# ap-pam-v3_2.net
KiCad netlist of a schematic drawn in Altium Designer
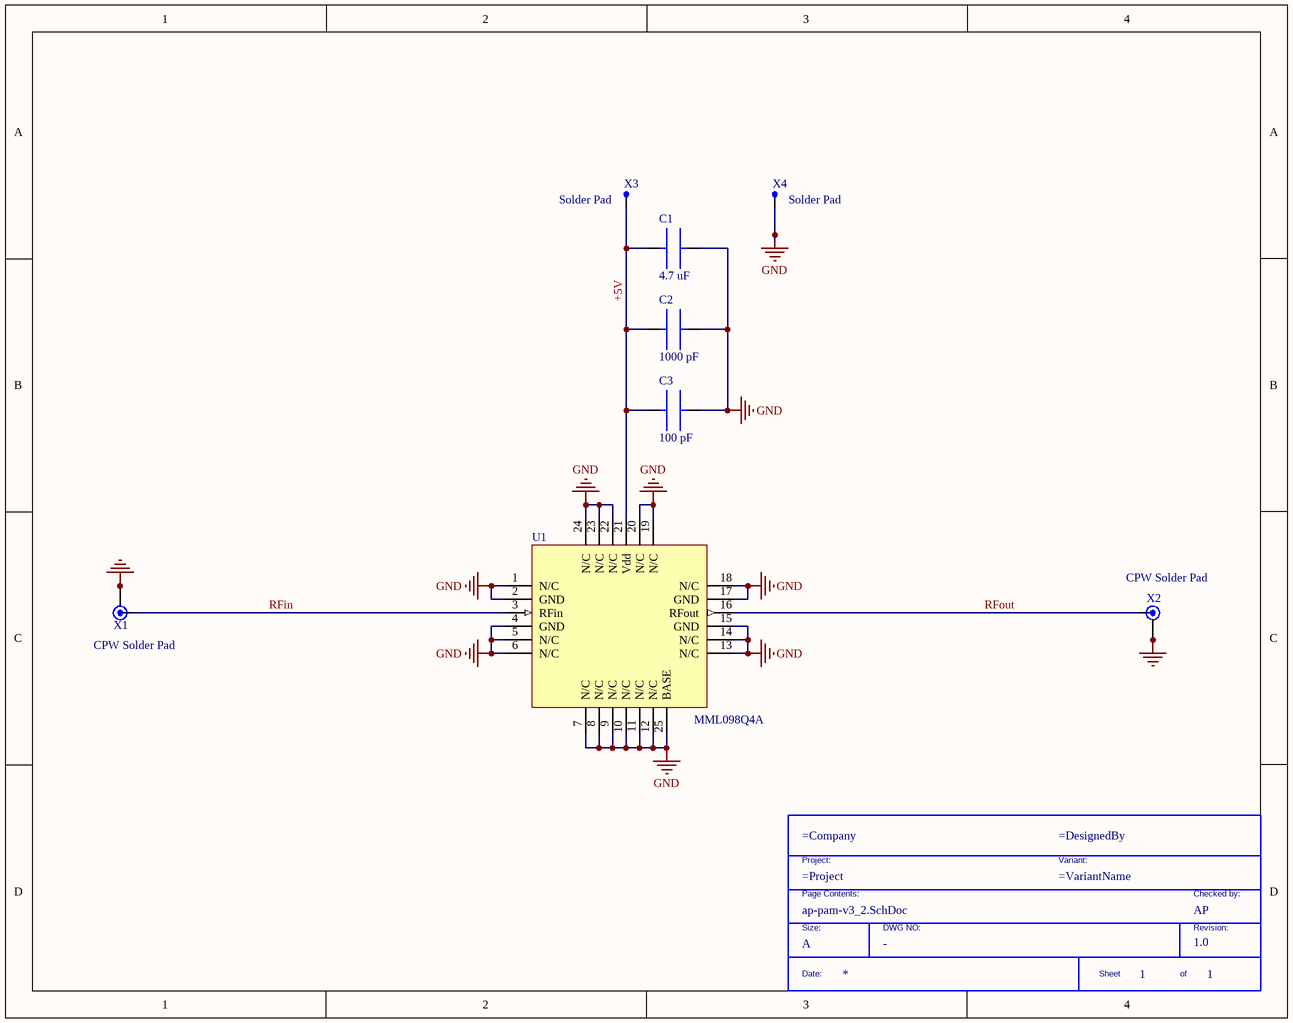
[diagram p0: ap-pam-v3_2.SchDoc]

(export (version "E")
  (design (tool "Eeschema 10.0.6"))
  (components
    (comp (ref "*")
      (value "~")
      (description "Standard Title Block")
      (fields (field (name "DWG NO") "-") (field (name "SIZE") "A") (field (name "CHECKED BY") "AP"))
      (libsource (lib "ap-pam") (part "TitleBlock"))
    )
    (comp (ref "C1")
      (value "4.7 uF")
      (footprint "C4_7uF")
      (fields
        (field (name "MANUFACTURER") "Vishay Sprague")
        (field (name "MANUFACTURER PART NUMBER") "TH3A475K010C2900")
      )
      (libsource (lib "ap-pam") (part "TH3A475K010C2900"))
    )
    (comp (ref "C2")
      (value "1000 pF")
      (footprint "C1000pF")
      (fields
        (field (name "MANUFACTURER") "Murata")
        (field (name "MANUFACTURER PART NUMBER") "GCM1885C1H102FA16D")
      )
      (libsource (lib "ap-pam") (part "GCM1885C1H102FA16D"))
    )
    (comp (ref "C3")
      (value "100 pF")
      (footprint "C100pF")
      (description "Multilayer Ceramic Capacitors MLCC - SMD/SMT 100 pF 100 VDC 1% 0402 C0G (NP0)")
      (fields
        (field (name "MANUFACTURER") "Murata")
        (field (name "MANUFACTURER PART NUMBER") "GRM1555C2A101FA01D")
      )
      (libsource (lib "ap-pam") (part "GRM1555C2A101FA01D"))
    )
    (comp (ref "U1")
      (value "MML098Q4A")
      (footprint "MML098Q4A")
      (libsource (lib "ap-pam") (part "MML098Q4A"))
    )
    (comp (ref "X1")
      (value "CPW Solder Pad")
      (footprint "CPW Edge Connector")
      (description "Solder pad for RF Coplanar Waveguide Rogers 4350B Thickness 0.020\" Copper 1oz")
      (libsource (lib "ap-pam") (part "RF  CPW Solder Pad"))
    )
    (comp (ref "X2")
      (value "CPW Solder Pad")
      (footprint "CPW Edge Connector")
      (description "Solder pad for RF Coplanar Waveguide Rogers 4350B Thickness 0.020\" Copper 1oz")
      (libsource (lib "ap-pam") (part "RF  CPW Solder Pad"))
    )
    (comp (ref "X3")
      (value "Solder Pad")
      (footprint "Solder Pad")
      (description "Pad to solder wires to")
      (libsource (lib "ap-pam") (part "Solder Pad"))
    )
    (comp (ref "X4")
      (value "Solder Pad")
      (footprint "Solder Pad")
      (description "Pad to solder wires to")
      (libsource (lib "ap-pam") (part "Solder Pad"))
    )
  )
  (nets
    (net (code "1") (name "/+5V") (class "Default")
      (node (ref "C1") (pin "1") (pinfunction "1_1") (pintype "passive"))
      (node (ref "C2") (pin "2") (pinfunction "2_2") (pintype "passive"))
      (node (ref "C3") (pin "2") (pinfunction "2_2") (pintype "passive"))
      (node (ref "U1") (pin "21") (pinfunction "Vdd_21") (pintype "power_in"))
      (node (ref "X3") (pin "1") (pinfunction "1_1") (pintype "passive"))
    )
    (net (code "2") (name "/RFin") (class "Default")
      (node (ref "U1") (pin "3") (pinfunction "RFin_3") (pintype "input"))
      (node (ref "X1") (pin "1") (pinfunction "1_1") (pintype "passive"))
    )
    (net (code "3") (name "/RFout") (class "Default")
      (node (ref "U1") (pin "16") (pinfunction "RFout_16") (pintype "output"))
      (node (ref "X2") (pin "1") (pinfunction "1_1") (pintype "passive"))
    )
    (net (code "4") (name "GND") (class "Default")
      (node (ref "C1") (pin "2") (pinfunction "2_2") (pintype "passive"))
      (node (ref "C2") (pin "1") (pinfunction "1_1") (pintype "passive"))
      (node (ref "C3") (pin "1") (pinfunction "1_1") (pintype "passive"))
      (node (ref "U1") (pin "1") (pinfunction "N/C_1") (pintype "passive"))
      (node (ref "U1") (pin "10") (pinfunction "N/C_10") (pintype "passive"))
      (node (ref "U1") (pin "11") (pinfunction "N/C_11") (pintype "passive"))
      (node (ref "U1") (pin "12") (pinfunction "N/C_12") (pintype "passive"))
      (node (ref "U1") (pin "13") (pinfunction "N/C_13") (pintype "passive"))
      (node (ref "U1") (pin "14") (pinfunction "N/C_14") (pintype "passive"))
      (node (ref "U1") (pin "15") (pinfunction "GND_15") (pintype "power_in"))
      (node (ref "U1") (pin "17") (pinfunction "GND_17") (pintype "power_in"))
      (node (ref "U1") (pin "18") (pinfunction "N/C_18") (pintype "passive"))
      (node (ref "U1") (pin "19") (pinfunction "N/C_19") (pintype "passive"))
      (node (ref "U1") (pin "2") (pinfunction "GND_2") (pintype "power_in"))
      (node (ref "U1") (pin "20") (pinfunction "N/C_20") (pintype "passive"))
      (node (ref "U1") (pin "22") (pinfunction "N/C_22") (pintype "passive"))
      (node (ref "U1") (pin "23") (pinfunction "N/C_23") (pintype "passive"))
      (node (ref "U1") (pin "24") (pinfunction "N/C_24") (pintype "passive"))
      (node (ref "U1") (pin "25") (pinfunction "BASE_25") (pintype "power_in"))
      (node (ref "U1") (pin "4") (pinfunction "GND_4") (pintype "power_in"))
      (node (ref "U1") (pin "5") (pinfunction "N/C_5") (pintype "passive"))
      (node (ref "U1") (pin "6") (pinfunction "N/C_6") (pintype "passive"))
      (node (ref "U1") (pin "7") (pinfunction "N/C_7") (pintype "passive"))
      (node (ref "U1") (pin "8") (pinfunction "N/C_8") (pintype "passive"))
      (node (ref "U1") (pin "9") (pinfunction "N/C_9") (pintype "passive"))
      (node (ref "X1") (pin "2") (pinfunction "2_2") (pintype "passive"))
      (node (ref "X1") (pin "3") (pinfunction "3_3") (pintype "passive"))
      (node (ref "X2") (pin "2") (pinfunction "2_2") (pintype "passive"))
      (node (ref "X2") (pin "3") (pinfunction "3_3") (pintype "passive"))
      (node (ref "X4") (pin "1") (pinfunction "1_1") (pintype "passive"))
    )
  )
)
